# DATN2022_DataReader.net
KiCad netlist of a schematic drawn in Altium Designer
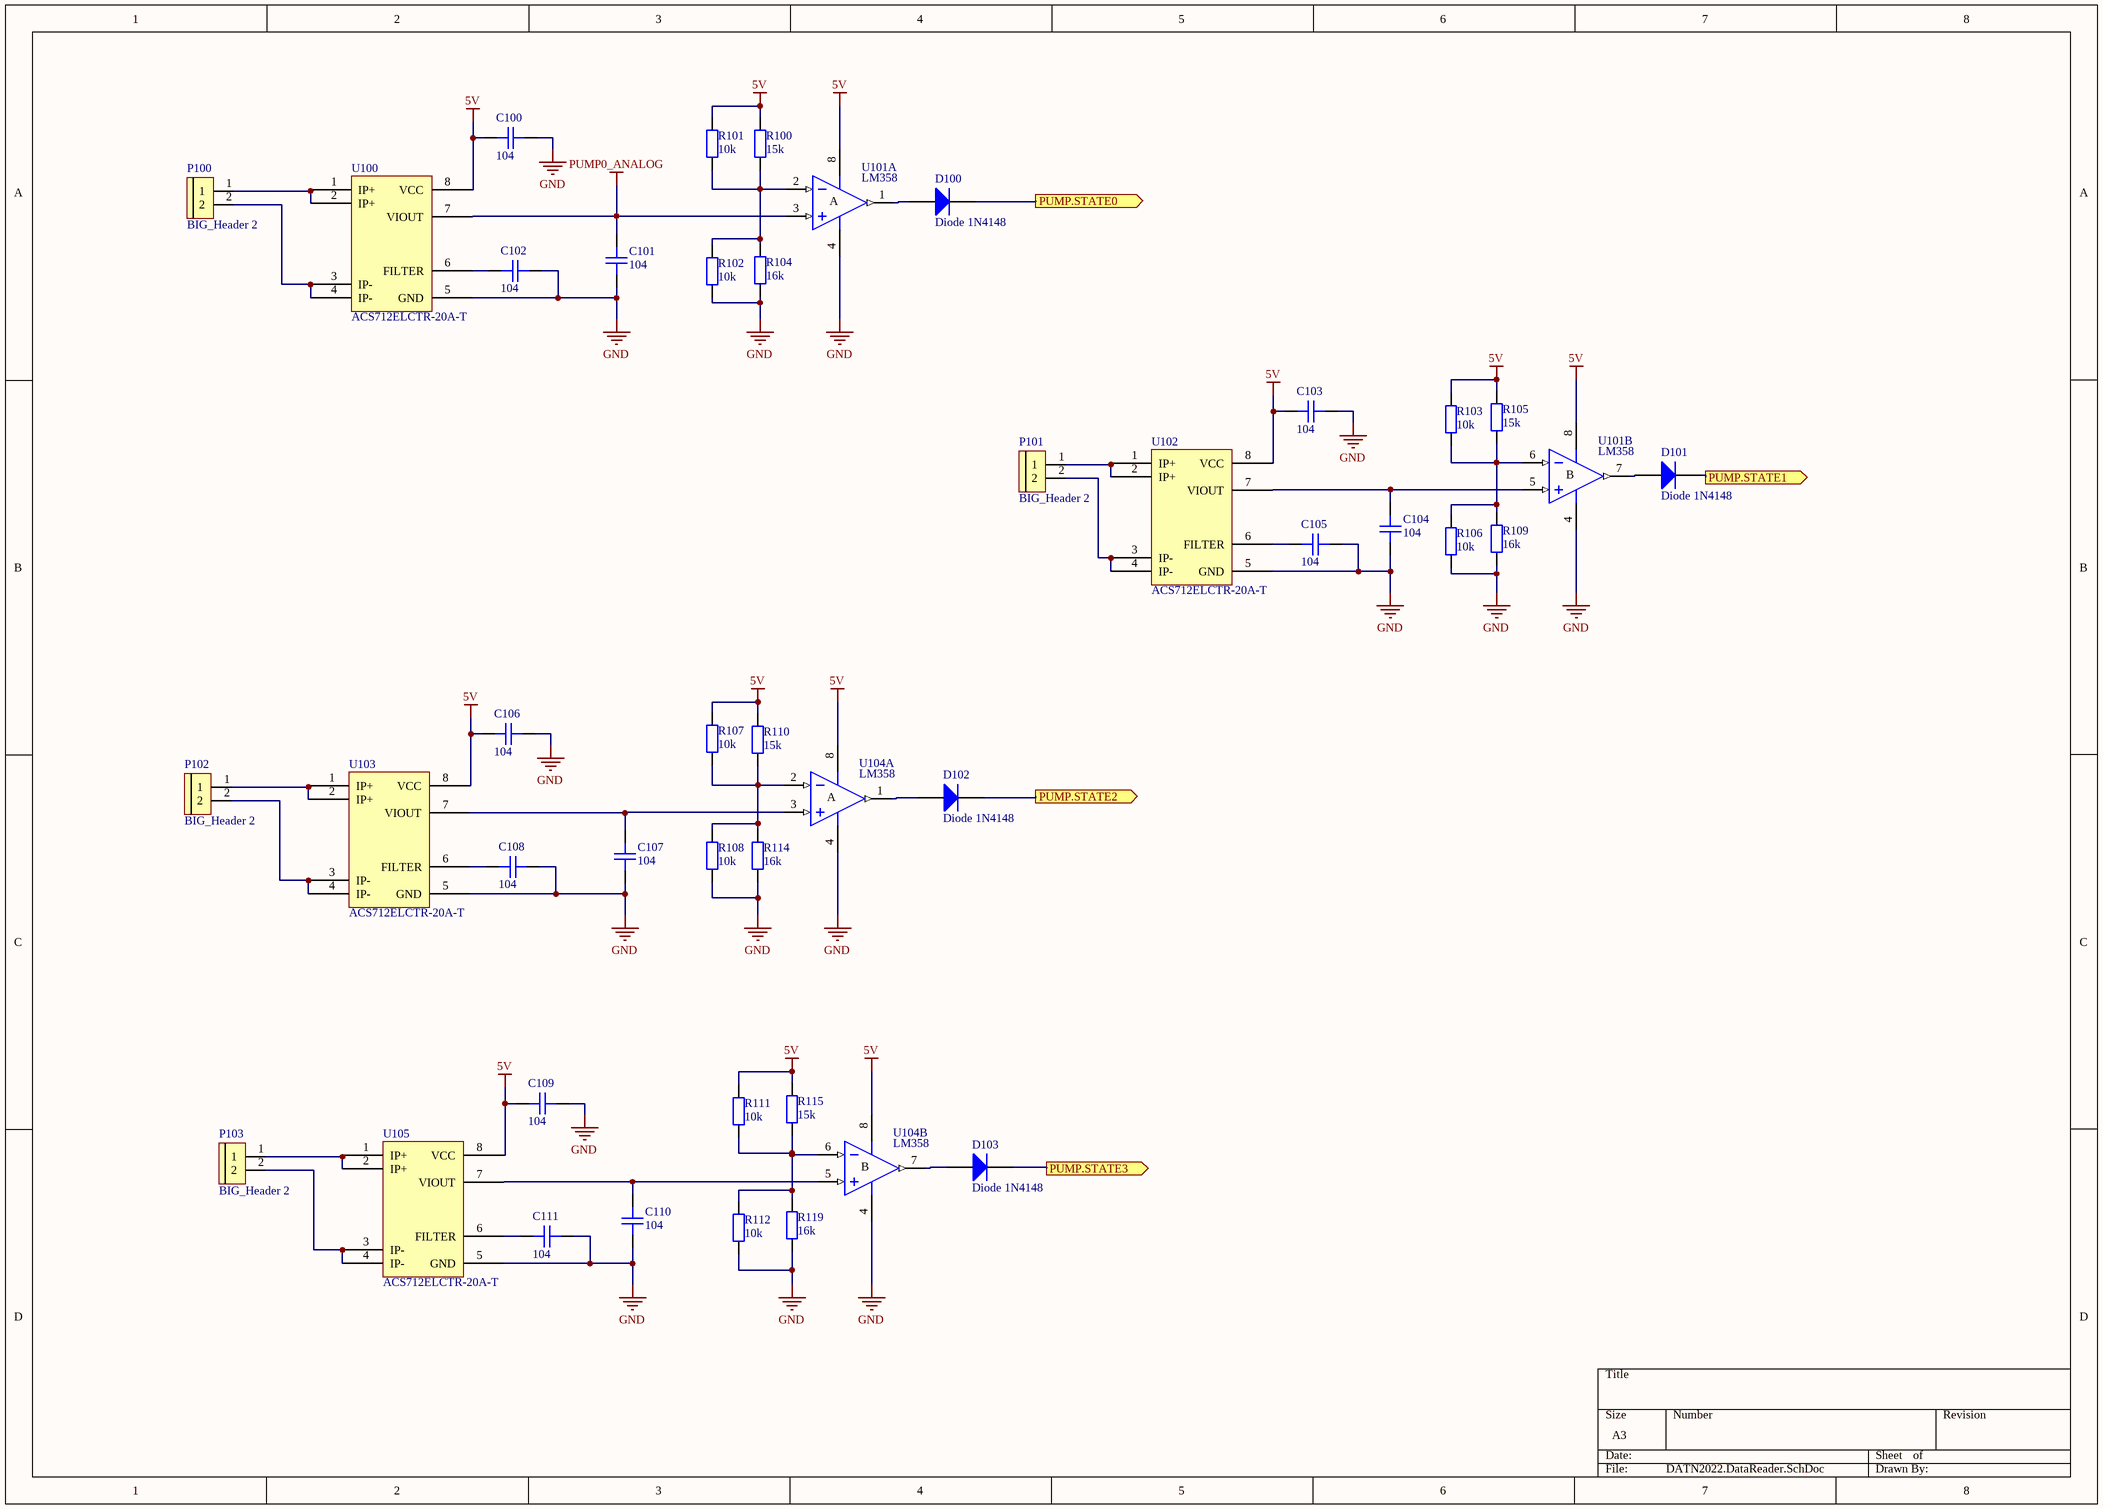
[diagram p0: DATN2022.DataReader.SchDoc]

(export (version "E")
  (design (tool "Eeschema 10.0.6"))
  (components
    (comp (ref "C100")
      (value "104")
      (footprint "CAP_CERAMIC_0805(2012mm)")
      (description "Capacitor Ceramic SMD 0805(2012)")
      (fields (field (name "PUBLISHER") "Altium Limited"))
      (libsource (lib "01.Capacitor") (part "Cap Cer 0805 (2012)"))
    )
    (comp (ref "C101")
      (value "104")
      (footprint "CAP_CERAMIC_0805(2012mm)")
      (description "Capacitor Ceramic SMD 0805(2012)")
      (fields (field (name "PUBLISHER") "Altium Limited"))
      (libsource (lib "01.Capacitor") (part "Cap Cer 0805 (2012)"))
    )
    (comp (ref "C102")
      (value "104")
      (footprint "CAP_CERAMIC_0805(2012mm)")
      (description "Capacitor Ceramic SMD 0805(2012)")
      (fields (field (name "PUBLISHER") "Altium Limited"))
      (libsource (lib "01.Capacitor") (part "Cap Cer 0805 (2012)"))
    )
    (comp (ref "C103")
      (value "104")
      (footprint "CAP_CERAMIC_0805(2012mm)")
      (description "Capacitor Ceramic SMD 0805(2012)")
      (fields (field (name "PUBLISHER") "Altium Limited"))
      (libsource (lib "01.Capacitor") (part "Cap Cer 0805 (2012)"))
    )
    (comp (ref "C104")
      (value "104")
      (footprint "CAP_CERAMIC_0805(2012mm)")
      (description "Capacitor Ceramic SMD 0805(2012)")
      (fields (field (name "PUBLISHER") "Altium Limited"))
      (libsource (lib "01.Capacitor") (part "Cap Cer 0805 (2012)"))
    )
    (comp (ref "C105")
      (value "104")
      (footprint "CAP_CERAMIC_0805(2012mm)")
      (description "Capacitor Ceramic SMD 0805(2012)")
      (fields (field (name "PUBLISHER") "Altium Limited"))
      (libsource (lib "01.Capacitor") (part "Cap Cer 0805 (2012)"))
    )
    (comp (ref "C106")
      (value "104")
      (footprint "CAP_CERAMIC_0805(2012mm)")
      (description "Capacitor Ceramic SMD 0805(2012)")
      (fields (field (name "PUBLISHER") "Altium Limited"))
      (libsource (lib "01.Capacitor") (part "Cap Cer 0805 (2012)"))
    )
    (comp (ref "C107")
      (value "104")
      (footprint "CAP_CERAMIC_0805(2012mm)")
      (description "Capacitor Ceramic SMD 0805(2012)")
      (fields (field (name "PUBLISHER") "Altium Limited"))
      (libsource (lib "01.Capacitor") (part "Cap Cer 0805 (2012)"))
    )
    (comp (ref "C108")
      (value "104")
      (footprint "CAP_CERAMIC_0805(2012mm)")
      (description "Capacitor Ceramic SMD 0805(2012)")
      (fields (field (name "PUBLISHER") "Altium Limited"))
      (libsource (lib "01.Capacitor") (part "Cap Cer 0805 (2012)"))
    )
    (comp (ref "C109")
      (value "104")
      (footprint "CAP_CERAMIC_0805(2012mm)")
      (description "Capacitor Ceramic SMD 0805(2012)")
      (fields (field (name "PUBLISHER") "Altium Limited"))
      (libsource (lib "01.Capacitor") (part "Cap Cer 0805 (2012)"))
    )
    (comp (ref "C110")
      (value "104")
      (footprint "CAP_CERAMIC_0805(2012mm)")
      (description "Capacitor Ceramic SMD 0805(2012)")
      (fields (field (name "PUBLISHER") "Altium Limited"))
      (libsource (lib "01.Capacitor") (part "Cap Cer 0805 (2012)"))
    )
    (comp (ref "C111")
      (value "104")
      (footprint "CAP_CERAMIC_0805(2012mm)")
      (description "Capacitor Ceramic SMD 0805(2012)")
      (fields (field (name "PUBLISHER") "Altium Limited"))
      (libsource (lib "01.Capacitor") (part "Cap Cer 0805 (2012)"))
    )
    (comp (ref "D100")
      (value "Diode 1N4148")
      (footprint "DO214AC_SMA_1808")
      (description "High Conductance Fast Diode")
      (fields (field (name "PUBLISHER") "Altium Limited"))
      (libsource (lib "04.Diode_Led") (part "Diode 1N4448"))
    )
    (comp (ref "D101")
      (value "Diode 1N4148")
      (footprint "DO214AC_SMA_1808")
      (description "High Conductance Fast Diode")
      (fields (field (name "PUBLISHER") "Altium Limited"))
      (libsource (lib "04.Diode_Led") (part "Diode 1N4448"))
    )
    (comp (ref "D102")
      (value "Diode 1N4148")
      (footprint "DO214AC_SMA_1808")
      (description "High Conductance Fast Diode")
      (fields (field (name "PUBLISHER") "Altium Limited"))
      (libsource (lib "04.Diode_Led") (part "Diode 1N4448"))
    )
    (comp (ref "D103")
      (value "Diode 1N4148")
      (footprint "DO214AC_SMA_1808")
      (description "High Conductance Fast Diode")
      (fields (field (name "PUBLISHER") "Altium Limited"))
      (libsource (lib "04.Diode_Led") (part "Diode 1N4448"))
    )
    (comp (ref "P100")
      (value "BIG_Header 2")
      (footprint "KF128-2P")
      (libsource (lib "08.Header") (part "BIG_Header 2"))
    )
    (comp (ref "P101")
      (value "BIG_Header 2")
      (footprint "KF128-2P")
      (libsource (lib "08.Header") (part "BIG_Header 2"))
    )
    (comp (ref "P102")
      (value "BIG_Header 2")
      (footprint "KF128-2P")
      (libsource (lib "08.Header") (part "BIG_Header 2"))
    )
    (comp (ref "P103")
      (value "BIG_Header 2")
      (footprint "KF128-2P")
      (libsource (lib "08.Header") (part "BIG_Header 2"))
    )
    (comp (ref "R100")
      (value "15k")
      (footprint "RES_0805(2012)")
      (description "Resistor SMD 0805")
      (fields (field (name "PUBLISHER") "Altium Limited"))
      (libsource (lib "02.Resistor") (part "R0805"))
    )
    (comp (ref "R101")
      (value "10k")
      (footprint "RES_0805(2012)")
      (description "Resistor SMD 0805")
      (fields (field (name "PUBLISHER") "Altium Limited"))
      (libsource (lib "") (part "R0805_1"))
    )
    (comp (ref "R102")
      (value "10k")
      (footprint "RES_0805(2012)")
      (description "Resistor SMD 0805")
      (fields (field (name "PUBLISHER") "Altium Limited"))
      (libsource (lib "") (part "R0805_1"))
    )
    (comp (ref "R103")
      (value "10k")
      (footprint "RES_0805(2012)")
      (description "Resistor SMD 0805")
      (fields (field (name "PUBLISHER") "Altium Limited"))
      (libsource (lib "") (part "R0805_1"))
    )
    (comp (ref "R104")
      (value "16k")
      (footprint "RES_0805(2012)")
      (description "Resistor SMD 0805")
      (fields (field (name "PUBLISHER") "Altium Limited"))
      (libsource (lib "02.Resistor") (part "R0805"))
    )
    (comp (ref "R105")
      (value "15k")
      (footprint "RES_0805(2012)")
      (description "Resistor SMD 0805")
      (fields (field (name "PUBLISHER") "Altium Limited"))
      (libsource (lib "02.Resistor") (part "R0805"))
    )
    (comp (ref "R106")
      (value "10k")
      (footprint "RES_0805(2012)")
      (description "Resistor SMD 0805")
      (fields (field (name "PUBLISHER") "Altium Limited"))
      (libsource (lib "") (part "R0805_1"))
    )
    (comp (ref "R107")
      (value "10k")
      (footprint "RES_0805(2012)")
      (description "Resistor SMD 0805")
      (fields (field (name "PUBLISHER") "Altium Limited"))
      (libsource (lib "") (part "R0805_1"))
    )
    (comp (ref "R108")
      (value "10k")
      (footprint "RES_0805(2012)")
      (description "Resistor SMD 0805")
      (fields (field (name "PUBLISHER") "Altium Limited"))
      (libsource (lib "") (part "R0805_1"))
    )
    (comp (ref "R109")
      (value "16k")
      (footprint "RES_0805(2012)")
      (description "Resistor SMD 0805")
      (fields (field (name "PUBLISHER") "Altium Limited"))
      (libsource (lib "02.Resistor") (part "R0805"))
    )
    (comp (ref "R110")
      (value "15k")
      (footprint "RES_0805(2012)")
      (description "Resistor SMD 0805")
      (fields (field (name "PUBLISHER") "Altium Limited"))
      (libsource (lib "02.Resistor") (part "R0805"))
    )
    (comp (ref "R111")
      (value "10k")
      (footprint "RES_0805(2012)")
      (description "Resistor SMD 0805")
      (fields (field (name "PUBLISHER") "Altium Limited"))
      (libsource (lib "") (part "R0805_1"))
    )
    (comp (ref "R112")
      (value "10k")
      (footprint "RES_0805(2012)")
      (description "Resistor SMD 0805")
      (fields (field (name "PUBLISHER") "Altium Limited"))
      (libsource (lib "") (part "R0805_1"))
    )
    (comp (ref "R114")
      (value "16k")
      (footprint "RES_0805(2012)")
      (description "Resistor SMD 0805")
      (fields (field (name "PUBLISHER") "Altium Limited"))
      (libsource (lib "02.Resistor") (part "R0805"))
    )
    (comp (ref "R115")
      (value "15k")
      (footprint "RES_0805(2012)")
      (description "Resistor SMD 0805")
      (fields (field (name "PUBLISHER") "Altium Limited"))
      (libsource (lib "02.Resistor") (part "R0805"))
    )
    (comp (ref "R119")
      (value "16k")
      (footprint "RES_0805(2012)")
      (description "Resistor SMD 0805")
      (fields (field (name "PUBLISHER") "Altium Limited"))
      (libsource (lib "02.Resistor") (part "R0805"))
    )
    (comp (ref "U100")
      (value "ACS712ELCTR-20A-T")
      (footprint "SOIC8")
      (description "Current meter IC")
      (libsource (lib "07.General IC") (part "ACS712ELCTR-20A-T"))
    )
    (comp (ref "U101")
      (value "LM358")
      (footprint "SOIC8")
      (description "Dual Operational Amplifier (JFET)")
      (fields
        (field (name "MANUFACTURER") "Texas Instruments")
        (field (name "MANUFACTURER PART NUMBER") "LM358DR")
        (field (name "CREATOR") "Nguyen Ba Bien")
      )
      (libsource (lib "07.General IC") (part "LM358"))
    )
    (comp (ref "U102")
      (value "ACS712ELCTR-20A-T")
      (footprint "SOIC8")
      (description "Current meter IC")
      (libsource (lib "07.General IC") (part "ACS712ELCTR-20A-T"))
    )
    (comp (ref "U103")
      (value "ACS712ELCTR-20A-T")
      (footprint "SOIC8")
      (description "Current meter IC")
      (libsource (lib "07.General IC") (part "ACS712ELCTR-20A-T"))
    )
    (comp (ref "U104")
      (value "LM358")
      (footprint "SOIC8")
      (description "Dual Operational Amplifier (JFET)")
      (fields
        (field (name "MANUFACTURER") "Texas Instruments")
        (field (name "MANUFACTURER PART NUMBER") "LM358DR")
        (field (name "CREATOR") "Nguyen Ba Bien")
      )
      (libsource (lib "07.General IC") (part "LM358"))
    )
    (comp (ref "U105")
      (value "ACS712ELCTR-20A-T")
      (footprint "SOIC8")
      (description "Current meter IC")
      (libsource (lib "07.General IC") (part "ACS712ELCTR-20A-T"))
    )
  )
  (nets
    (net (code "1") (name "/PUMP.STATE0") (class "Default")
      (node (ref "D100") (pin "2") (pinfunction "K_2") (pintype "passive"))
    )
    (net (code "2") (name "/PUMP.STATE1") (class "Default")
      (node (ref "D101") (pin "2") (pinfunction "K_2") (pintype "passive"))
    )
    (net (code "3") (name "/PUMP.STATE2") (class "Default")
      (node (ref "D102") (pin "2") (pinfunction "K_2") (pintype "passive"))
    )
    (net (code "4") (name "/PUMP.STATE3") (class "Default")
      (node (ref "D103") (pin "2") (pinfunction "K_2") (pintype "passive"))
    )
    (net (code "5") (name "5V") (class "Default")
      (node (ref "C100") (pin "2") (pinfunction "2_2") (pintype "passive"))
      (node (ref "C103") (pin "2") (pinfunction "2_2") (pintype "passive"))
      (node (ref "C106") (pin "2") (pinfunction "2_2") (pintype "passive"))
      (node (ref "C109") (pin "2") (pinfunction "2_2") (pintype "passive"))
      (node (ref "R100") (pin "2") (pinfunction "2_2") (pintype "passive"))
      (node (ref "R101") (pin "1") (pinfunction "1_1") (pintype "passive"))
      (node (ref "R103") (pin "1") (pinfunction "1_1") (pintype "passive"))
      (node (ref "R105") (pin "2") (pinfunction "2_2") (pintype "passive"))
      (node (ref "R107") (pin "1") (pinfunction "1_1") (pintype "passive"))
      (node (ref "R110") (pin "2") (pinfunction "2_2") (pintype "passive"))
      (node (ref "R111") (pin "1") (pinfunction "1_1") (pintype "passive"))
      (node (ref "R115") (pin "2") (pinfunction "2_2") (pintype "passive"))
      (node (ref "U100") (pin "8") (pinfunction "VCC_8") (pintype "passive"))
      (node (ref "U101") (pin "8") (pinfunction "V+_8") (pintype "power_in"))
      (node (ref "U102") (pin "8") (pinfunction "VCC_8") (pintype "passive"))
      (node (ref "U103") (pin "8") (pinfunction "VCC_8") (pintype "passive"))
      (node (ref "U104") (pin "8") (pinfunction "V+_8") (pintype "power_in"))
      (node (ref "U105") (pin "8") (pinfunction "VCC_8") (pintype "passive"))
    )
    (net (code "6") (name "GND") (class "Default")
      (node (ref "C100") (pin "1") (pinfunction "1_1") (pintype "passive"))
      (node (ref "C101") (pin "2") (pinfunction "2_2") (pintype "passive"))
      (node (ref "C102") (pin "2") (pinfunction "2_2") (pintype "passive"))
      (node (ref "C103") (pin "1") (pinfunction "1_1") (pintype "passive"))
      (node (ref "C104") (pin "2") (pinfunction "2_2") (pintype "passive"))
      (node (ref "C105") (pin "2") (pinfunction "2_2") (pintype "passive"))
      (node (ref "C106") (pin "1") (pinfunction "1_1") (pintype "passive"))
      (node (ref "C107") (pin "2") (pinfunction "2_2") (pintype "passive"))
      (node (ref "C108") (pin "2") (pinfunction "2_2") (pintype "passive"))
      (node (ref "C109") (pin "1") (pinfunction "1_1") (pintype "passive"))
      (node (ref "C110") (pin "2") (pinfunction "2_2") (pintype "passive"))
      (node (ref "C111") (pin "2") (pinfunction "2_2") (pintype "passive"))
      (node (ref "R102") (pin "2") (pinfunction "2_2") (pintype "passive"))
      (node (ref "R104") (pin "1") (pinfunction "1_1") (pintype "passive"))
      (node (ref "R106") (pin "2") (pinfunction "2_2") (pintype "passive"))
      (node (ref "R108") (pin "2") (pinfunction "2_2") (pintype "passive"))
      (node (ref "R109") (pin "1") (pinfunction "1_1") (pintype "passive"))
      (node (ref "R112") (pin "2") (pinfunction "2_2") (pintype "passive"))
      (node (ref "R114") (pin "1") (pinfunction "1_1") (pintype "passive"))
      (node (ref "R119") (pin "1") (pinfunction "1_1") (pintype "passive"))
      (node (ref "U100") (pin "5") (pinfunction "GND_5") (pintype "passive"))
      (node (ref "U101") (pin "4") (pinfunction "V-_4") (pintype "power_in"))
      (node (ref "U102") (pin "5") (pinfunction "GND_5") (pintype "passive"))
      (node (ref "U103") (pin "5") (pinfunction "GND_5") (pintype "passive"))
      (node (ref "U104") (pin "4") (pinfunction "V-_4") (pintype "power_in"))
      (node (ref "U105") (pin "5") (pinfunction "GND_5") (pintype "passive"))
    )
    (net (code "7") (name "Net-(D100-A)") (class "Default")
      (node (ref "D100") (pin "1") (pinfunction "A_1") (pintype "passive"))
      (node (ref "U101") (pin "1") (pinfunction "OUT_1") (pintype "output"))
    )
    (net (code "8") (name "Net-(D101-A)") (class "Default")
      (node (ref "D101") (pin "1") (pinfunction "A_1") (pintype "passive"))
      (node (ref "U101") (pin "7") (pinfunction "OUT_7") (pintype "output"))
    )
    (net (code "9") (name "Net-(D102-A)") (class "Default")
      (node (ref "D102") (pin "1") (pinfunction "A_1") (pintype "passive"))
      (node (ref "U104") (pin "1") (pinfunction "OUT_1") (pintype "output"))
    )
    (net (code "10") (name "Net-(D103-A)") (class "Default")
      (node (ref "D103") (pin "1") (pinfunction "A_1") (pintype "passive"))
      (node (ref "U104") (pin "7") (pinfunction "OUT_7") (pintype "output"))
    )
    (net (code "11") (name "Net-(P100-Pad1)") (class "Default")
      (node (ref "P100") (pin "1") (pinfunction "1_1") (pintype "passive"))
      (node (ref "U100") (pin "1") (pinfunction "IP+_1") (pintype "passive"))
      (node (ref "U100") (pin "2") (pinfunction "IP+_2") (pintype "passive"))
    )
    (net (code "12") (name "Net-(P100-Pad2)") (class "Default")
      (node (ref "P100") (pin "2") (pinfunction "2_2") (pintype "passive"))
      (node (ref "U100") (pin "3") (pinfunction "IP-_3") (pintype "passive"))
      (node (ref "U100") (pin "4") (pinfunction "IP-_4") (pintype "passive"))
    )
    (net (code "13") (name "Net-(P101-Pad1)") (class "Default")
      (node (ref "P101") (pin "1") (pinfunction "1_1") (pintype "passive"))
      (node (ref "U102") (pin "1") (pinfunction "IP+_1") (pintype "passive"))
      (node (ref "U102") (pin "2") (pinfunction "IP+_2") (pintype "passive"))
    )
    (net (code "14") (name "Net-(P101-Pad2)") (class "Default")
      (node (ref "P101") (pin "2") (pinfunction "2_2") (pintype "passive"))
      (node (ref "U102") (pin "3") (pinfunction "IP-_3") (pintype "passive"))
      (node (ref "U102") (pin "4") (pinfunction "IP-_4") (pintype "passive"))
    )
    (net (code "15") (name "Net-(P102-Pad1)") (class "Default")
      (node (ref "P102") (pin "1") (pinfunction "1_1") (pintype "passive"))
      (node (ref "U103") (pin "1") (pinfunction "IP+_1") (pintype "passive"))
      (node (ref "U103") (pin "2") (pinfunction "IP+_2") (pintype "passive"))
    )
    (net (code "16") (name "Net-(P102-Pad2)") (class "Default")
      (node (ref "P102") (pin "2") (pinfunction "2_2") (pintype "passive"))
      (node (ref "U103") (pin "3") (pinfunction "IP-_3") (pintype "passive"))
      (node (ref "U103") (pin "4") (pinfunction "IP-_4") (pintype "passive"))
    )
    (net (code "17") (name "Net-(P103-Pad1)") (class "Default")
      (node (ref "P103") (pin "1") (pinfunction "1_1") (pintype "passive"))
      (node (ref "U105") (pin "1") (pinfunction "IP+_1") (pintype "passive"))
      (node (ref "U105") (pin "2") (pinfunction "IP+_2") (pintype "passive"))
    )
    (net (code "18") (name "Net-(P103-Pad2)") (class "Default")
      (node (ref "P103") (pin "2") (pinfunction "2_2") (pintype "passive"))
      (node (ref "U105") (pin "3") (pinfunction "IP-_3") (pintype "passive"))
      (node (ref "U105") (pin "4") (pinfunction "IP-_4") (pintype "passive"))
    )
    (net (code "19") (name "Net-(U100-FILTER)") (class "Default")
      (node (ref "C102") (pin "1") (pinfunction "1_1") (pintype "passive"))
      (node (ref "U100") (pin "6") (pinfunction "FILTER_6") (pintype "passive"))
    )
    (net (code "20") (name "Net-(U101A-IN-)") (class "Default")
      (node (ref "R100") (pin "1") (pinfunction "1_1") (pintype "passive"))
      (node (ref "R101") (pin "2") (pinfunction "2_2") (pintype "passive"))
      (node (ref "R102") (pin "1") (pinfunction "1_1") (pintype "passive"))
      (node (ref "R104") (pin "2") (pinfunction "2_2") (pintype "passive"))
      (node (ref "U101") (pin "2") (pinfunction "IN-_2") (pintype "input"))
    )
    (net (code "21") (name "Net-(U101B-IN+)") (class "Default")
      (node (ref "C104") (pin "1") (pinfunction "1_1") (pintype "passive"))
      (node (ref "U101") (pin "5") (pinfunction "IN+_5") (pintype "input"))
      (node (ref "U102") (pin "7") (pinfunction "VIOUT_7") (pintype "passive"))
    )
    (net (code "22") (name "Net-(U101B-IN-)") (class "Default")
      (node (ref "R103") (pin "2") (pinfunction "2_2") (pintype "passive"))
      (node (ref "R105") (pin "1") (pinfunction "1_1") (pintype "passive"))
      (node (ref "R106") (pin "1") (pinfunction "1_1") (pintype "passive"))
      (node (ref "R109") (pin "2") (pinfunction "2_2") (pintype "passive"))
      (node (ref "U101") (pin "6") (pinfunction "IN-_6") (pintype "input"))
    )
    (net (code "23") (name "Net-(U102-FILTER)") (class "Default")
      (node (ref "C105") (pin "1") (pinfunction "1_1") (pintype "passive"))
      (node (ref "U102") (pin "6") (pinfunction "FILTER_6") (pintype "passive"))
    )
    (net (code "24") (name "Net-(U103-FILTER)") (class "Default")
      (node (ref "C108") (pin "1") (pinfunction "1_1") (pintype "passive"))
      (node (ref "U103") (pin "6") (pinfunction "FILTER_6") (pintype "passive"))
    )
    (net (code "25") (name "Net-(U103-VIOUT)") (class "Default")
      (node (ref "C107") (pin "1") (pinfunction "1_1") (pintype "passive"))
      (node (ref "U103") (pin "7") (pinfunction "VIOUT_7") (pintype "passive"))
      (node (ref "U104") (pin "3") (pinfunction "IN+_3") (pintype "input"))
    )
    (net (code "26") (name "Net-(U104A-IN-)") (class "Default")
      (node (ref "R107") (pin "2") (pinfunction "2_2") (pintype "passive"))
      (node (ref "R108") (pin "1") (pinfunction "1_1") (pintype "passive"))
      (node (ref "R110") (pin "1") (pinfunction "1_1") (pintype "passive"))
      (node (ref "R114") (pin "2") (pinfunction "2_2") (pintype "passive"))
      (node (ref "U104") (pin "2") (pinfunction "IN-_2") (pintype "input"))
    )
    (net (code "27") (name "Net-(U104B-IN+)") (class "Default")
      (node (ref "C110") (pin "1") (pinfunction "1_1") (pintype "passive"))
      (node (ref "U104") (pin "5") (pinfunction "IN+_5") (pintype "input"))
      (node (ref "U105") (pin "7") (pinfunction "VIOUT_7") (pintype "passive"))
    )
    (net (code "28") (name "Net-(U104B-IN-)") (class "Default")
      (node (ref "R111") (pin "2") (pinfunction "2_2") (pintype "passive"))
      (node (ref "R112") (pin "1") (pinfunction "1_1") (pintype "passive"))
      (node (ref "R115") (pin "1") (pinfunction "1_1") (pintype "passive"))
      (node (ref "R119") (pin "2") (pinfunction "2_2") (pintype "passive"))
      (node (ref "U104") (pin "6") (pinfunction "IN-_6") (pintype "input"))
    )
    (net (code "29") (name "Net-(U105-FILTER)") (class "Default")
      (node (ref "C111") (pin "1") (pinfunction "1_1") (pintype "passive"))
      (node (ref "U105") (pin "6") (pinfunction "FILTER_6") (pintype "passive"))
    )
    (net (code "30") (name "PUMP0_ANALOG") (class "Default")
      (node (ref "C101") (pin "1") (pinfunction "1_1") (pintype "passive"))
      (node (ref "U100") (pin "7") (pinfunction "VIOUT_7") (pintype "passive"))
      (node (ref "U101") (pin "3") (pinfunction "IN+_3") (pintype "input"))
    )
  )
)
